# OSO-MISC-20-020_Programming_Board_for_Ri.net
KiCad netlist of a schematic drawn in EAGLE
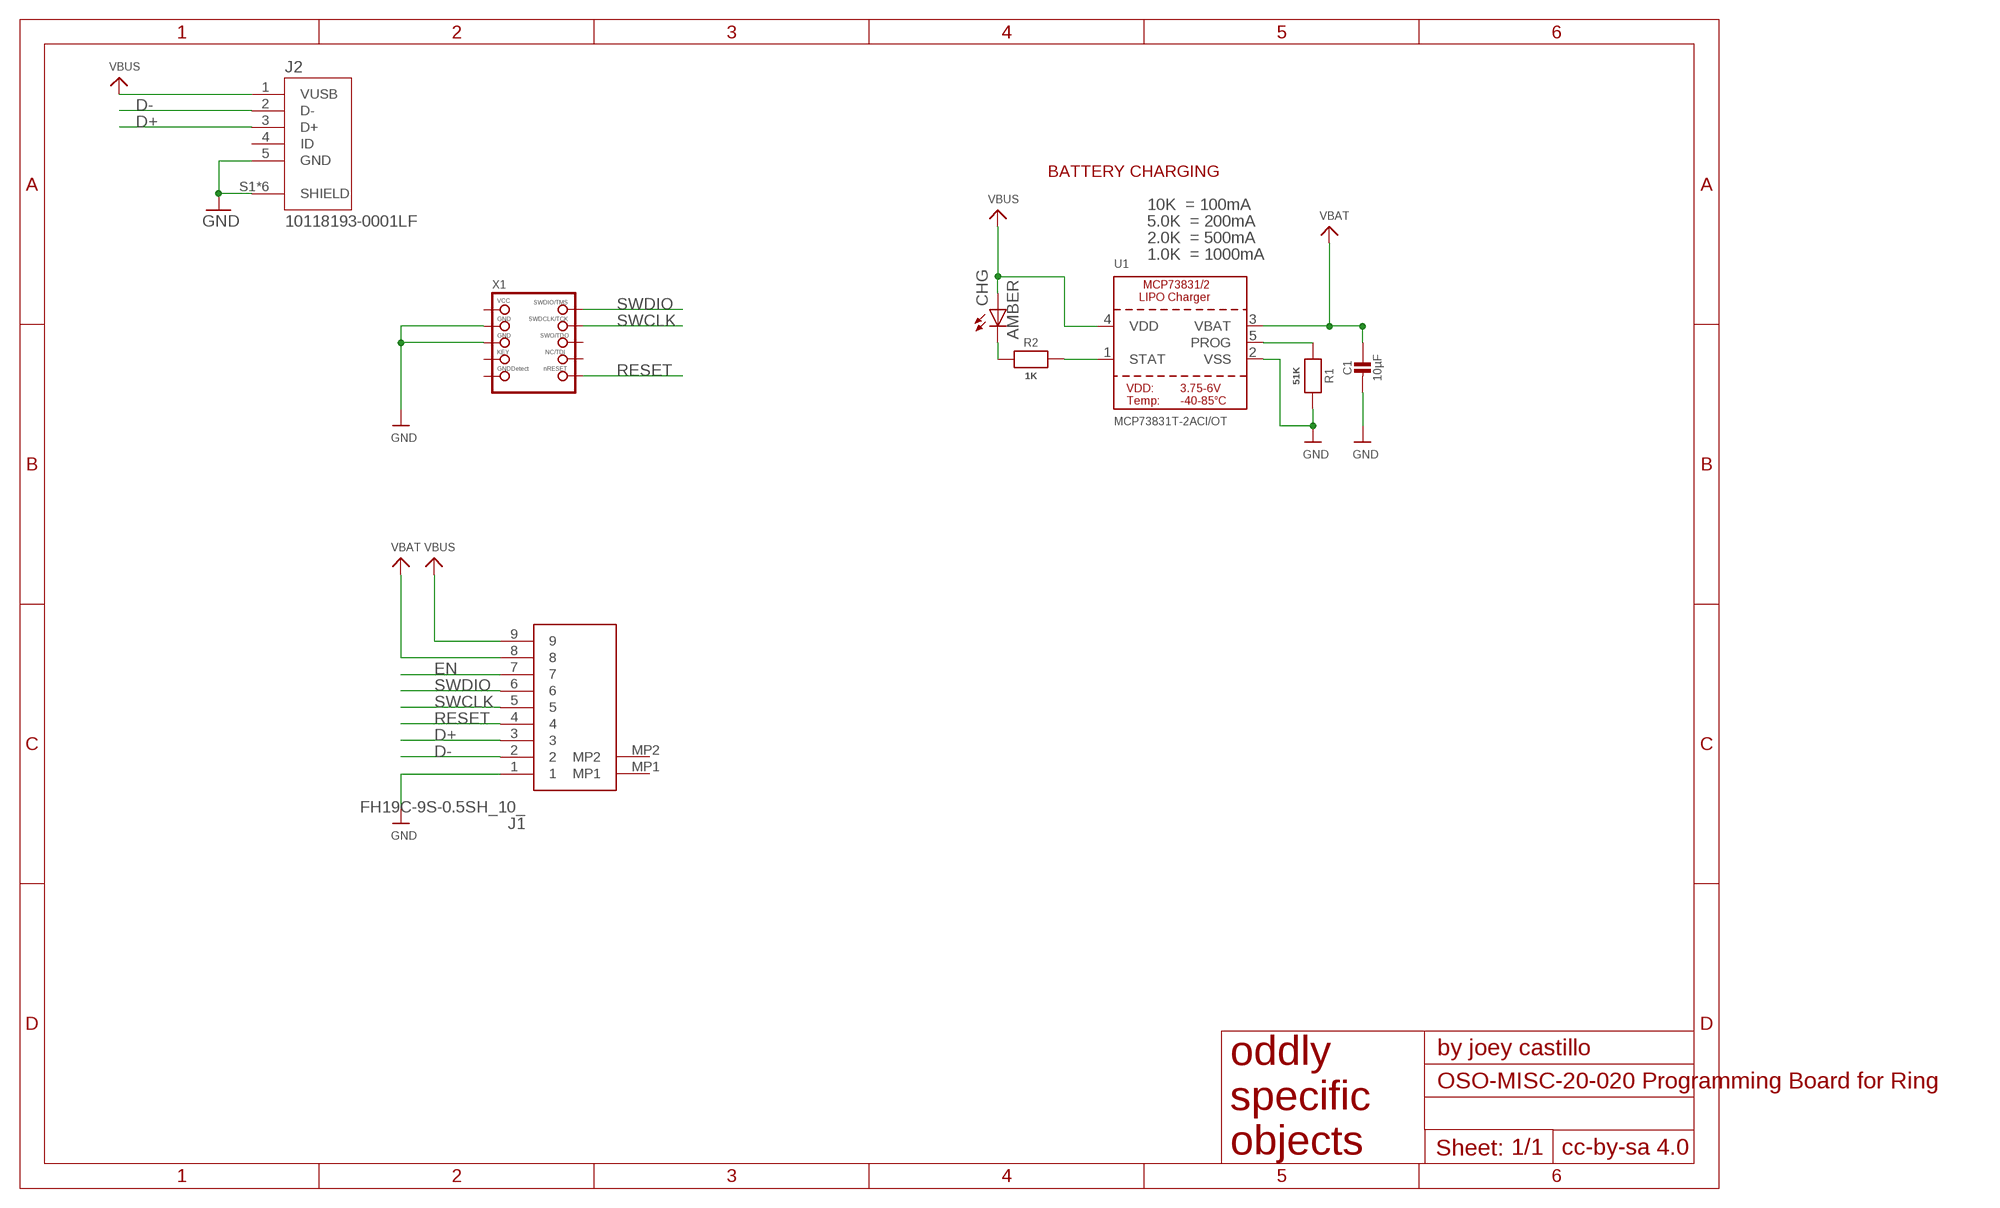
[diagram p0: schematic, sheet 1]

(export (version "E")
  (design (tool "Eeschema 10.0.6"))
  (components
    (comp (ref "C1")
      (value "10µF")
      (footprint "eagle-import:0805-NO")
      (libsource (lib "eagle-import") (part "CAP_CERAMIC0805-NOOUTLINE"))
    )
    (comp (ref "CHG")
      (value "AMBER")
      (footprint "eagle-import:CHIPLED_0805")
      (libsource (lib "eagle-import") (part "LEDCHIPLED_0805"))
    )
    (comp (ref "J1")
      (value "FH19C-9S-0.5SH_10_")
      (footprint "eagle-import:FH19C9S05SH10")
      (fields
        (field (name "MANUFACTURER_PART_NUMBER") "FH19C-9S-0.5SH(10)")
        (field (name "MOUSER_PART_NUMBER") "798-FH19C9S05SH10")
      )
      (libsource (lib "eagle-import") (part "FH19C-9S-0.5SH_10_"))
    )
    (comp (ref "J2")
      (value "10118193-0001LF")
      (footprint "eagle-import:FCI_10118193-0001LF")
      (fields (field (name "DIGI-KEY_PART_NUMBER") "609-4616-1-ND") (field (name "MF") "Amphenol ICC"))
      (libsource (lib "eagle-import") (part "10118193-0001LF"))
    )
    (comp (ref "R1")
      (value "51K")
      (footprint "eagle-import:0805-NO")
      (libsource (lib "eagle-import") (part "RESISTOR0805_NOOUTLINE"))
    )
    (comp (ref "R2")
      (value "1K")
      (footprint "eagle-import:0805-NO")
      (libsource (lib "eagle-import") (part "RESISTOR0805_NOOUTLINE"))
    )
    (comp (ref "U1")
      (value "MCP73831T-2ACI/OT")
      (footprint "eagle-import:SOT23-5")
      (libsource (lib "eagle-import") (part "MCP73831/2"))
    )
    (comp (ref "X1")
      (value "JTAG-CORTEXBOX")
      (footprint "eagle-import:2X05_1.27MM_BOX_NOPOSTS")
      (libsource (lib "eagle-import") (part "JTAG-CORTEXBOX"))
    )
  )
  (nets
    (net (code "1") (name "/D+") (class "Default")
      (node (ref "J1") (pin "3") (pinfunction "3_3") (pintype "bidirectional"))
      (node (ref "J2") (pin "3") (pinfunction "D+_3") (pintype "passive"))
    )
    (net (code "2") (name "/D-") (class "Default")
      (node (ref "J1") (pin "2") (pinfunction "2_2") (pintype "bidirectional"))
      (node (ref "J2") (pin "2") (pinfunction "D-_2") (pintype "passive"))
    )
    (net (code "3") (name "/EN") (class "Default")
      (node (ref "J1") (pin "7") (pinfunction "7_7") (pintype "bidirectional"))
    )
    (net (code "4") (name "/RESET") (class "Default")
      (node (ref "J1") (pin "4") (pinfunction "4_4") (pintype "bidirectional"))
      (node (ref "X1") (pin "10") (pinfunction "NRESET_10") (pintype "bidirectional"))
    )
    (net (code "5") (name "/SWCLK") (class "Default")
      (node (ref "J1") (pin "5") (pinfunction "5_5") (pintype "bidirectional"))
      (node (ref "X1") (pin "4") (pinfunction "SWDCLK_4") (pintype "bidirectional"))
    )
    (net (code "6") (name "/SWDIO") (class "Default")
      (node (ref "J1") (pin "6") (pinfunction "6_6") (pintype "bidirectional"))
      (node (ref "X1") (pin "2") (pinfunction "SWDIO_2") (pintype "bidirectional"))
    )
    (net (code "7") (name "/VCC") (class "Default")
      (node (ref "X1") (pin "1") (pinfunction "VCC_1") (pintype "power_in"))
    )
    (net (code "8") (name "GND") (class "Default")
      (node (ref "C1") (pin "2") (pinfunction "2_2") (pintype "passive"))
      (node (ref "J1") (pin "1") (pinfunction "1_1") (pintype "bidirectional"))
      (node (ref "J2") (pin "5") (pinfunction "GND_5") (pintype "passive"))
      (node (ref "J2") (pin "S1") (pinfunction "SHIELD_S1") (pintype "passive"))
      (node (ref "J2") (pin "S2") (pinfunction "SHIELD_S2") (pintype "passive"))
      (node (ref "J2") (pin "S3") (pinfunction "SHIELD_S3") (pintype "passive"))
      (node (ref "J2") (pin "S4") (pinfunction "SHIELD_S4") (pintype "passive"))
      (node (ref "J2") (pin "S5") (pinfunction "SHIELD_S5") (pintype "passive"))
      (node (ref "J2") (pin "S6") (pinfunction "SHIELD_S6") (pintype "passive"))
      (node (ref "R1") (pin "2") (pinfunction "2_2") (pintype "passive"))
      (node (ref "U1") (pin "2") (pinfunction "VSS_2") (pintype "power_in"))
      (node (ref "X1") (pin "3") (pinfunction "GND_3") (pintype "power_in"))
      (node (ref "X1") (pin "5") (pinfunction "GND_5") (pintype "power_in"))
    )
    (net (code "9") (name "Net-(CHG-PadC)") (class "Default")
      (node (ref "CHG") (pin "C") (pinfunction "C_C") (pintype "passive"))
      (node (ref "R2") (pin "1") (pinfunction "1_1") (pintype "passive"))
    )
    (net (code "10") (name "Net-(U1-PROG)") (class "Default")
      (node (ref "R1") (pin "1") (pinfunction "1_1") (pintype "passive"))
      (node (ref "U1") (pin "5") (pinfunction "PROG_5") (pintype "input"))
    )
    (net (code "11") (name "Net-(U1-STAT)") (class "Default")
      (node (ref "R2") (pin "2") (pinfunction "2_2") (pintype "passive"))
      (node (ref "U1") (pin "1") (pinfunction "STAT_1") (pintype "output"))
    )
    (net (code "12") (name "VBAT") (class "Default")
      (node (ref "C1") (pin "1") (pinfunction "1_1") (pintype "passive"))
      (node (ref "J1") (pin "8") (pinfunction "8_8") (pintype "bidirectional"))
      (node (ref "U1") (pin "3") (pinfunction "VBAT_3") (pintype "power_in"))
    )
    (net (code "13") (name "VBUS") (class "Default")
      (node (ref "CHG") (pin "A") (pinfunction "A_A") (pintype "passive"))
      (node (ref "J1") (pin "9") (pinfunction "9_9") (pintype "bidirectional"))
      (node (ref "J2") (pin "1") (pinfunction "VUSB_1") (pintype "passive"))
      (node (ref "U1") (pin "4") (pinfunction "VDD_4") (pintype "power_in"))
    )
    (net (code "14") (name "unconnected-(J1-PadMP1)") (class "Default")
      (node (ref "J1") (pin "MP1") (pinfunction "MP1_MP1") (pintype "bidirectional"))
    )
    (net (code "15") (name "unconnected-(J1-PadMP2)") (class "Default")
      (node (ref "J1") (pin "MP2") (pinfunction "MP2_MP2") (pintype "bidirectional"))
    )
    (net (code "16") (name "unconnected-(J2-ID-Pad4)") (class "Default")
      (node (ref "J2") (pin "4") (pinfunction "ID_4") (pintype "passive"))
    )
    (net (code "17") (name "unconnected-(X1-GNDDETECT-Pad9)") (class "Default")
      (node (ref "X1") (pin "9") (pinfunction "GNDDETECT_9") (pintype "bidirectional"))
    )
    (net (code "18") (name "unconnected-(X1-KEY-Pad7)") (class "Default")
      (node (ref "X1") (pin "7") (pinfunction "KEY_7") (pintype "bidirectional"))
    )
    (net (code "19") (name "unconnected-(X1-SWO-Pad6)") (class "Default")
      (node (ref "X1") (pin "6") (pinfunction "SWO_6") (pintype "bidirectional"))
    )
    (net (code "20") (name "unconnected-(X1-TDI-Pad8)") (class "Default")
      (node (ref "X1") (pin "8") (pinfunction "TDI_8") (pintype "bidirectional"))
    )
  )
)
